# main.net
KiCad netlist of a schematic drawn in Altium Designer
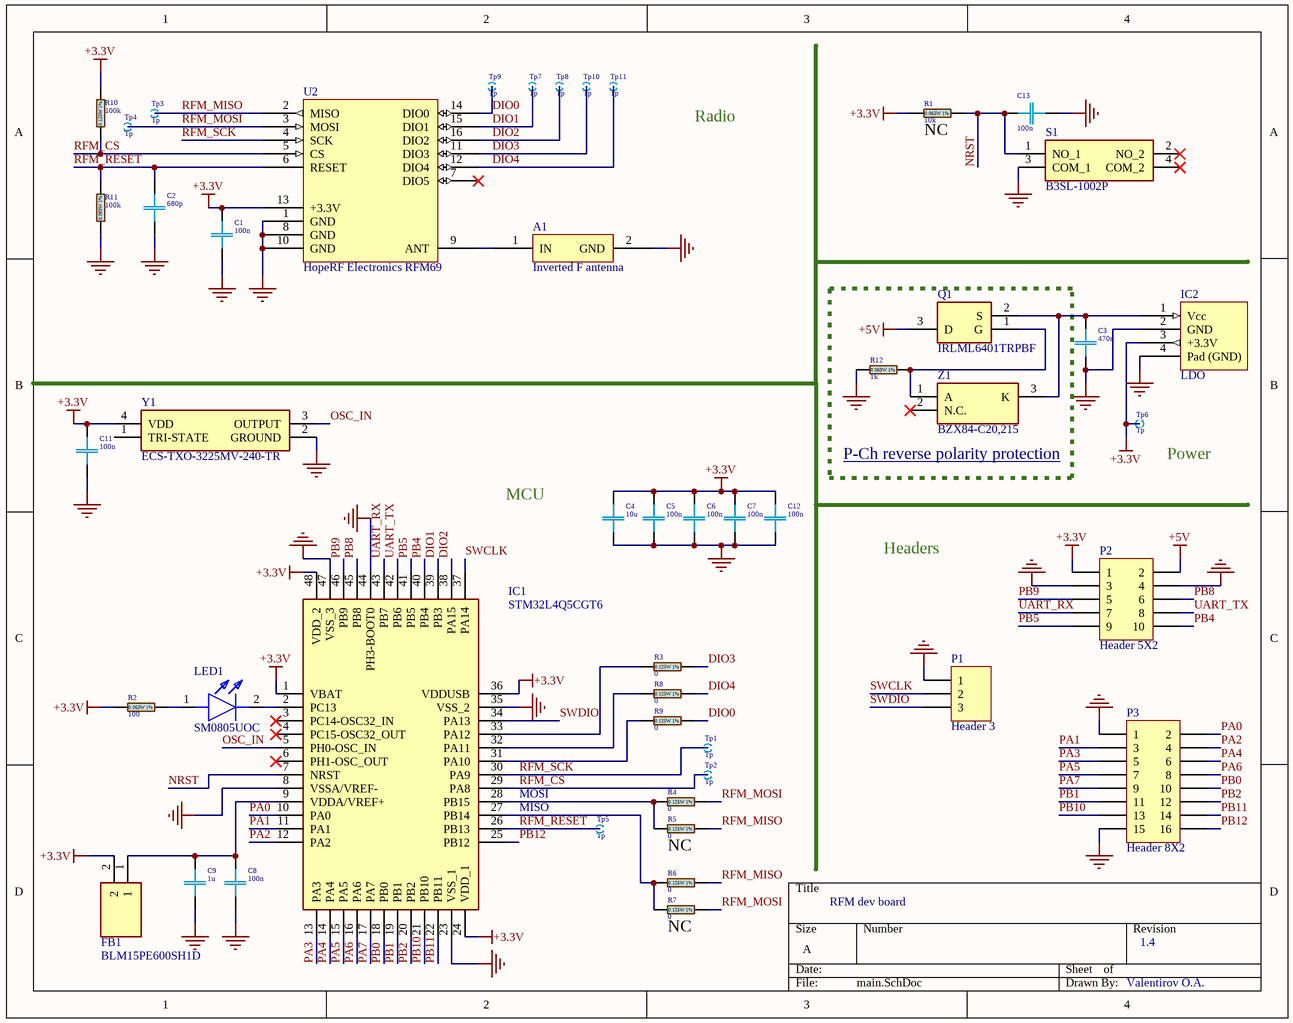
[diagram p0: main.SchDoc]

(export (version "E")
  (design (tool "Eeschema 10.0.6"))
  (components
    (comp (ref "A1")
      (value "Inverted F antenna")
      (footprint "Invertef_F-footprint")
      (libsource (lib "radio") (part "inverted_F"))
    )
    (comp (ref "C1")
      (value "100n")
      (footprint "C 0402(1005)x0.5")
      (description "SMD 0402     16V X5R 10%")
      (fields (field (name "MANUFACTURER") "Samsung") (field (name "PUBLISHER") "Hefest"))
      (libsource (lib "SMD Passive") (part "C 0402    16V X5R - 0*"))
    )
    (comp (ref "C2")
      (value "680p")
      (footprint "C 0402(1005)x0.5")
      (description "SMD 0402     16V X5R 10%")
      (fields (field (name "MANUFACTURER") "Samsung") (field (name "PUBLISHER") "Hefest"))
      (libsource (lib "SMD Passive") (part "C 0402    16V X5R - 0*"))
    )
    (comp (ref "C3")
      (value "470n")
      (footprint "C 0603(1608)x0.8")
      (description "SMD 0603     50V X7R   5%")
      (fields
        (field (name "PART NUMBER") "CL10B104JB8NNNC")
        (field (name "MANUFACTURER") "Samsung")
        (field (name "PUBLISHER") "Hefest")
      )
      (libsource (lib "SMD Passive") (part "C 0603    50V X7R - 100n"))
    )
    (comp (ref "C4")
      (value "10u")
      (footprint "C 0402(1005)x0.5")
      (description "SMD 0402     16V X5R 10%")
      (fields (field (name "MANUFACTURER") "Samsung") (field (name "PUBLISHER") "Hefest"))
      (libsource (lib "SMD Passive") (part "C 0402    16V X5R - 0*"))
    )
    (comp (ref "C5")
      (value "100n")
      (footprint "C 0402(1005)x0.5")
      (description "SMD 0402     16V X5R 10%")
      (fields (field (name "MANUFACTURER") "Samsung") (field (name "PUBLISHER") "Hefest"))
      (libsource (lib "SMD Passive") (part "C 0402    16V X5R - 0*"))
    )
    (comp (ref "C6")
      (value "100n")
      (footprint "C 0402(1005)x0.5")
      (description "SMD 0402     16V X5R 10%")
      (fields (field (name "MANUFACTURER") "Samsung") (field (name "PUBLISHER") "Hefest"))
      (libsource (lib "SMD Passive") (part "C 0402    16V X5R - 0*"))
    )
    (comp (ref "C7")
      (value "100n")
      (footprint "C 0402(1005)x0.5")
      (description "SMD 0402     16V X5R 10%")
      (fields (field (name "MANUFACTURER") "Samsung") (field (name "PUBLISHER") "Hefest"))
      (libsource (lib "SMD Passive") (part "C 0402    16V X5R - 0*"))
    )
    (comp (ref "C8")
      (value "100n")
      (footprint "C 0402(1005)x0.5")
      (description "SMD 0402     16V X5R 10%")
      (fields (field (name "MANUFACTURER") "Samsung") (field (name "PUBLISHER") "Hefest"))
      (libsource (lib "SMD Passive") (part "C 0402    16V X5R - 0*"))
    )
    (comp (ref "C9")
      (value "1u")
      (footprint "C 0402(1005)x0.5")
      (description "SMD 0402     16V X5R 10%")
      (fields (field (name "MANUFACTURER") "Samsung") (field (name "PUBLISHER") "Hefest"))
      (libsource (lib "SMD Passive") (part "C 0402    16V X5R - 0*"))
    )
    (comp (ref "C11")
      (value "100n")
      (footprint "C 0402(1005)x0.5")
      (description "SMD 0402     16V X5R 10%")
      (fields (field (name "MANUFACTURER") "Samsung") (field (name "PUBLISHER") "Hefest"))
      (libsource (lib "SMD Passive") (part "C 0402    16V X5R - 0*"))
    )
    (comp (ref "C12")
      (value "100n")
      (footprint "C 0402(1005)x0.5")
      (description "SMD 0402     16V X5R 10%")
      (fields (field (name "MANUFACTURER") "Samsung") (field (name "PUBLISHER") "Hefest"))
      (libsource (lib "SMD Passive") (part "C 0402    16V X5R - 0*"))
    )
    (comp (ref "C13")
      (value "100n")
      (footprint "C 0402(1005)x0.5")
      (description "SMD 0402     16V X5R 10%")
      (fields (field (name "MANUFACTURER") "Samsung") (field (name "PUBLISHER") "Hefest"))
      (libsource (lib "SMD Passive") (part "C 0402    16V X5R - 0*"))
    )
    (comp (ref "FB1")
      (value "BLM15PE600SH1D")
      (footprint "SamacSys:NFZ15SG152SN10B")
      (description "Ferrite Bead")
      (fields (field (name "MOUSER PART NUMBER") "81-BLM15PE600SH1D"))
      (libsource (lib "SamacSys") (part "BLM15PE600SH1D"))
    )
    (comp (ref "IC1")
      (value "STM32L4Q5CGT6")
      (footprint "SamacSys:QFP50P900X900X160-48N")
      (description "Integrated Circuit")
      (fields (field (name "MOUSER PART NUMBER") "511-STM32L4Q5CGT6"))
      (libsource (lib "SamacSys") (part "STM32L4Q5CGT6"))
    )
    (comp (ref "IC2")
      (value "LDO")
      (footprint "SOT230P700X180-4N")
      (description "LDO voltage regulator. In 4.5V - 5.5V. Out 3.3V")
      (libsource (lib "power") (part "LM3940IMP-3.3"))
    )
    (comp (ref "LED1")
      (value "SM0805UOC")
      (footprint "SamacSys:SM0805UOC")
      (description "LED")
      (fields (field (name "MOUSER PART NUMBER") "749-SM0805UOC"))
      (libsource (lib "SamacSys") (part "SM0805UOC"))
    )
    (comp (ref "P1")
      (value "Header 3")
      (footprint "HDR1X3")
      (description "Header, 3-Pin")
      (fields (field (name "PUBLISHER") "Altium Limited"))
      (libsource (lib "Miscellaneous Connectors") (part "Header 3"))
    )
    (comp (ref "P2")
      (value "Header 5X2")
      (footprint "HDR2X5")
      (description "Header, 5-Pin, Dual row")
      (fields (field (name "PUBLISHER") "Altium Limited"))
      (libsource (lib "Miscellaneous Connectors") (part "Header 5X2"))
    )
    (comp (ref "P3")
      (value "Header 8X2")
      (footprint "HDR2X8")
      (description "Header, 8-Pin, Dual row")
      (fields (field (name "PUBLISHER") "Altium Limited"))
      (libsource (lib "Miscellaneous Connectors") (part "Header 8X2"))
    )
    (comp (ref "Q1")
      (value "IRLML6401TRPBF")
      (footprint "SamacSys:SOT95P237X112-3N")
      (description "Transistor")
      (fields (field (name "MOUSER PART NUMBER") "942-IRLML6401TRPBF"))
      (libsource (lib "SamacSys") (part "IRLML6401TRPBF"))
    )
    (comp (ref "R1")
      (value "10k")
      (footprint "R 0402(1005)-1%")
      (description "SMD 0402 0.063W 1%   50V")
      (fields
        (field (name "MANUFACTURER") "YAGEO")
        (field (name "POWER") "0.0625W")
        (field (name "PUBLISHER") "Hefest")
      )
      (libsource (lib "") (part "R 0402-1%_1"))
    )
    (comp (ref "R2")
      (value "100")
      (footprint "R 0402(1005)-1%")
      (description "SMD 0402 0.063W 1%   50V")
      (fields
        (field (name "MANUFACTURER") "YAGEO")
        (field (name "POWER") "0.0625W")
        (field (name "PUBLISHER") "Hefest")
      )
      (libsource (lib "") (part "R 0402-1%_1"))
    )
    (comp (ref "R3")
      (value "0")
      (footprint "R 0805(2012)-1%")
      (description "SMD 0805 0.125W 1% 150V")
      (fields
        (field (name "MANUFACTURER") "YAGEO")
        (field (name "POWER") "0.125W")
        (field (name "PUBLISHER") "Hefest")
      )
      (libsource (lib "SMD Passive") (part "R 0805-1%"))
    )
    (comp (ref "R4")
      (value "0")
      (footprint "R 0805(2012)-1%")
      (description "SMD 0805 0.125W 1% 150V")
      (fields
        (field (name "MANUFACTURER") "YAGEO")
        (field (name "POWER") "0.125W")
        (field (name "PUBLISHER") "Hefest")
      )
      (libsource (lib "SMD Passive") (part "R 0805-1%"))
    )
    (comp (ref "R5")
      (value "0")
      (footprint "R 0805(2012)-1%")
      (description "SMD 0805 0.125W 1% 150V")
      (fields
        (field (name "MANUFACTURER") "YAGEO")
        (field (name "POWER") "0.125W")
        (field (name "PUBLISHER") "Hefest")
      )
      (libsource (lib "SMD Passive") (part "R 0805-1%"))
    )
    (comp (ref "R6")
      (value "0")
      (footprint "R 0805(2012)-1%")
      (description "SMD 0805 0.125W 1% 150V")
      (fields
        (field (name "MANUFACTURER") "YAGEO")
        (field (name "POWER") "0.125W")
        (field (name "PUBLISHER") "Hefest")
      )
      (libsource (lib "SMD Passive") (part "R 0805-1%"))
    )
    (comp (ref "R7")
      (value "0")
      (footprint "R 0805(2012)-1%")
      (description "SMD 0805 0.125W 1% 150V")
      (fields
        (field (name "MANUFACTURER") "YAGEO")
        (field (name "POWER") "0.125W")
        (field (name "PUBLISHER") "Hefest")
      )
      (libsource (lib "SMD Passive") (part "R 0805-1%"))
    )
    (comp (ref "R8")
      (value "0")
      (footprint "R 0805(2012)-1%")
      (description "SMD 0805 0.125W 1% 150V")
      (fields
        (field (name "MANUFACTURER") "YAGEO")
        (field (name "POWER") "0.125W")
        (field (name "PUBLISHER") "Hefest")
      )
      (libsource (lib "SMD Passive") (part "R 0805-1%"))
    )
    (comp (ref "R9")
      (value "0")
      (footprint "R 0805(2012)-1%")
      (description "SMD 0805 0.125W 1% 150V")
      (fields
        (field (name "MANUFACTURER") "YAGEO")
        (field (name "POWER") "0.125W")
        (field (name "PUBLISHER") "Hefest")
      )
      (libsource (lib "SMD Passive") (part "R 0805-1%"))
    )
    (comp (ref "R10")
      (value "100k")
      (footprint "R 0805(2012)-1%")
      (description "SMD 0805 0.125W 1% 150V")
      (fields
        (field (name "MANUFACTURER") "YAGEO")
        (field (name "POWER") "0.125W")
        (field (name "PUBLISHER") "Hefest")
      )
      (libsource (lib "") (part "R 0805-1%_1"))
    )
    (comp (ref "R11")
      (value "100k")
      (footprint "R 0402(1005)-1%")
      (description "SMD 0402 0.063W 1%   50V")
      (fields
        (field (name "MANUFACTURER") "YAGEO")
        (field (name "POWER") "0.0625W")
        (field (name "PUBLISHER") "Hefest")
      )
      (libsource (lib "SMD Passive") (part "R 0402-1%"))
    )
    (comp (ref "R12")
      (value "1k")
      (footprint "R 0402(1005)-1%")
      (description "SMD 0402 0.063W 1%   50V")
      (fields
        (field (name "MANUFACTURER") "YAGEO")
        (field (name "POWER") "0.0625W")
        (field (name "PUBLISHER") "Hefest")
      )
      (libsource (lib "") (part "R 0402-1%_1"))
    )
    (comp (ref "S1")
      (value "B3SL-1002P")
      (footprint "SamacSys:B3SL1002P")
      (description "Switch")
      (fields (field (name "MOUSER PART NUMBER") "653-B3SL-1002P"))
      (libsource (lib "SamacSys") (part "B3SL-1002P"))
    )
    (comp (ref "Tp1")
      (value "Tp")
      (footprint "Tp-0.5")
      (description "TestPoint")
      (fields (field (name "PUBLISHER") "Hefest"))
      (libsource (lib "SMD Passive") (part "Tp"))
    )
    (comp (ref "Tp2")
      (value "Tp")
      (footprint "Tp-0.5")
      (description "TestPoint")
      (fields (field (name "PUBLISHER") "Hefest"))
      (libsource (lib "SMD Passive") (part "Tp"))
    )
    (comp (ref "Tp3")
      (value "Tp")
      (footprint "Tp-0.5")
      (description "TestPoint")
      (fields (field (name "PUBLISHER") "Hefest"))
      (libsource (lib "SMD Passive") (part "Tp"))
    )
    (comp (ref "Tp4")
      (value "Tp")
      (footprint "Tp-0.5")
      (description "TestPoint")
      (fields (field (name "PUBLISHER") "Hefest"))
      (libsource (lib "SMD Passive") (part "Tp"))
    )
    (comp (ref "Tp5")
      (value "Tp")
      (footprint "Tp-0.5")
      (description "TestPoint")
      (fields (field (name "PUBLISHER") "Hefest"))
      (libsource (lib "SMD Passive") (part "Tp"))
    )
    (comp (ref "Tp6")
      (value "Tp")
      (footprint "Tp-0.5")
      (description "TestPoint")
      (fields (field (name "PUBLISHER") "Hefest"))
      (libsource (lib "SMD Passive") (part "Tp"))
    )
    (comp (ref "Tp7")
      (value "Tp")
      (footprint "Tp-0.5")
      (description "TestPoint")
      (fields (field (name "PUBLISHER") "Hefest"))
      (libsource (lib "SMD Passive") (part "Tp"))
    )
    (comp (ref "Tp8")
      (value "Tp")
      (footprint "Tp-0.5")
      (description "TestPoint")
      (fields (field (name "PUBLISHER") "Hefest"))
      (libsource (lib "SMD Passive") (part "Tp"))
    )
    (comp (ref "Tp9")
      (value "Tp")
      (footprint "Tp-0.5")
      (description "TestPoint")
      (fields (field (name "PUBLISHER") "Hefest"))
      (libsource (lib "SMD Passive") (part "Tp"))
    )
    (comp (ref "Tp10")
      (value "Tp")
      (footprint "Tp-0.5")
      (description "TestPoint")
      (fields (field (name "PUBLISHER") "Hefest"))
      (libsource (lib "SMD Passive") (part "Tp"))
    )
    (comp (ref "Tp11")
      (value "Tp")
      (footprint "Tp-0.5")
      (description "TestPoint")
      (fields (field (name "PUBLISHER") "Hefest"))
      (libsource (lib "SMD Passive") (part "Tp"))
    )
    (comp (ref "U2")
      (value "HopeRF Electronics RFM69")
      (footprint "CAC-200P1600X1600-16N")
      (libsource (lib "radio") (part "RFM69"))
    )
    (comp (ref "Y1")
      (value "ECS-TXO-3225MV-240-TR")
      (footprint "SamacSys:ECSTXO3225MV240TR")
      (description "Crystal or Oscillator")
      (fields (field (name "MOUSER PART NUMBER") "520-TXO-3225MV-240-T"))
      (libsource (lib "SamacSys") (part "ECS-TXO-3225MV-240-TR"))
    )
    (comp (ref "Z1")
      (value "BZX84-C20,215")
      (footprint "SamacSys:BZX84C20215")
      (description "Zener Diode")
      (fields (field (name "MOUSER PART NUMBER") "771-BZX84-C20-T/R"))
      (libsource (lib "SamacSys") (part "BZX84-C20,215"))
    )
  )
  (nets
    (net (code "1") (name "+3.3V") (class "Default")
      (node (ref "C1") (pin "1") (pinfunction "1_1") (pintype "passive"))
      (node (ref "C11") (pin "1") (pinfunction "1_1") (pintype "passive"))
      (node (ref "C12") (pin "1") (pinfunction "1_1") (pintype "passive"))
      (node (ref "C4") (pin "1") (pinfunction "1_1") (pintype "passive"))
      (node (ref "C5") (pin "1") (pinfunction "1_1") (pintype "passive"))
      (node (ref "C6") (pin "1") (pinfunction "1_1") (pintype "passive"))
      (node (ref "C7") (pin "1") (pinfunction "1_1") (pintype "passive"))
      (node (ref "FB1") (pin "2") (pinfunction "2_2") (pintype "passive"))
      (node (ref "IC1") (pin "1") (pinfunction "VBAT_1") (pintype "passive"))
      (node (ref "IC1") (pin "24") (pinfunction "VDD_1_24") (pintype "passive"))
      (node (ref "IC1") (pin "36") (pinfunction "VDDUSB_36") (pintype "passive"))
      (node (ref "IC1") (pin "48") (pinfunction "VDD_2_48") (pintype "passive"))
      (node (ref "IC2") (pin "3") (pinfunction "+3.3V_3") (pintype "output"))
      (node (ref "P2") (pin "1") (pinfunction "1_1") (pintype "passive"))
      (node (ref "R1") (pin "1") (pinfunction "1_1") (pintype "passive"))
      (node (ref "R10") (pin "2") (pinfunction "2_2") (pintype "passive"))
      (node (ref "R2") (pin "1") (pinfunction "1_1") (pintype "passive"))
      (node (ref "Tp6") (pin "1") (pinfunction "1_1") (pintype "passive"))
      (node (ref "U2") (pin "13") (pinfunction "+3.3V_13") (pintype "passive"))
      (node (ref "Y1") (pin "4") (pinfunction "VDD_4") (pintype "passive"))
    )
    (net (code "2") (name "+5V") (class "Default")
      (node (ref "P2") (pin "2") (pinfunction "2_2") (pintype "passive"))
      (node (ref "Q1") (pin "3") (pinfunction "D_3") (pintype "passive"))
    )
    (net (code "3") (name "/DIO0") (class "Default")
      (node (ref "R9") (pin "2") (pinfunction "2_2") (pintype "passive"))
      (node (ref "Tp9") (pin "1") (pinfunction "1_1") (pintype "passive"))
      (node (ref "U2") (pin "14") (pinfunction "DIO0_14") (pintype "bidirectional"))
    )
    (net (code "4") (name "/DIO1") (class "Default")
      (node (ref "IC1") (pin "39") (pinfunction "PB3_39") (pintype "passive"))
      (node (ref "Tp7") (pin "1") (pinfunction "1_1") (pintype "passive"))
      (node (ref "U2") (pin "15") (pinfunction "DIO1_15") (pintype "bidirectional"))
    )
    (net (code "5") (name "/DIO2") (class "Default")
      (node (ref "IC1") (pin "38") (pinfunction "PA15_38") (pintype "passive"))
      (node (ref "Tp8") (pin "1") (pinfunction "1_1") (pintype "passive"))
      (node (ref "U2") (pin "16") (pinfunction "DIO2_16") (pintype "bidirectional"))
    )
    (net (code "6") (name "/DIO3") (class "Default")
      (node (ref "R3") (pin "2") (pinfunction "2_2") (pintype "passive"))
      (node (ref "Tp10") (pin "1") (pinfunction "1_1") (pintype "passive"))
      (node (ref "U2") (pin "11") (pinfunction "DIO3_11") (pintype "bidirectional"))
    )
    (net (code "7") (name "/DIO4") (class "Default")
      (node (ref "R8") (pin "2") (pinfunction "2_2") (pintype "passive"))
      (node (ref "Tp11") (pin "1") (pinfunction "1_1") (pintype "passive"))
      (node (ref "U2") (pin "12") (pinfunction "DIO4_12") (pintype "bidirectional"))
    )
    (net (code "8") (name "/NRST") (class "Default")
      (node (ref "C13") (pin "1") (pinfunction "1_1") (pintype "passive"))
      (node (ref "IC1") (pin "7") (pinfunction "NRST_7") (pintype "passive"))
      (node (ref "R1") (pin "2") (pinfunction "2_2") (pintype "passive"))
      (node (ref "S1") (pin "1") (pinfunction "NO_1_1") (pintype "passive"))
    )
    (net (code "9") (name "/OSC_IN") (class "Default")
      (node (ref "IC1") (pin "5") (pinfunction "PH0-OSC_IN_5") (pintype "passive"))
      (node (ref "Y1") (pin "3") (pinfunction "OUTPUT_3") (pintype "passive"))
    )
    (net (code "10") (name "/PA0") (class "Default")
      (node (ref "IC1") (pin "10") (pinfunction "PA0_10") (pintype "passive"))
      (node (ref "P3") (pin "2") (pinfunction "2_2") (pintype "passive"))
    )
    (net (code "11") (name "/PA1") (class "Default")
      (node (ref "IC1") (pin "11") (pinfunction "PA1_11") (pintype "passive"))
      (node (ref "P3") (pin "3") (pinfunction "3_3") (pintype "passive"))
    )
    (net (code "12") (name "/PA2") (class "Default")
      (node (ref "IC1") (pin "12") (pinfunction "PA2_12") (pintype "passive"))
      (node (ref "P3") (pin "4") (pinfunction "4_4") (pintype "passive"))
    )
    (net (code "13") (name "/PA3") (class "Default")
      (node (ref "IC1") (pin "13") (pinfunction "PA3_13") (pintype "passive"))
      (node (ref "P3") (pin "5") (pinfunction "5_5") (pintype "passive"))
    )
    (net (code "14") (name "/PA4") (class "Default")
      (node (ref "IC1") (pin "14") (pinfunction "PA4_14") (pintype "passive"))
      (node (ref "P3") (pin "6") (pinfunction "6_6") (pintype "passive"))
    )
    (net (code "15") (name "/PA5") (class "Default")
      (node (ref "IC1") (pin "15") (pinfunction "PA5_15") (pintype "passive"))
      (node (ref "P3") (pin "7") (pinfunction "7_7") (pintype "passive"))
    )
    (net (code "16") (name "/PA6") (class "Default")
      (node (ref "IC1") (pin "16") (pinfunction "PA6_16") (pintype "passive"))
      (node (ref "P3") (pin "8") (pinfunction "8_8") (pintype "passive"))
    )
    (net (code "17") (name "/PA7") (class "Default")
      (node (ref "IC1") (pin "17") (pinfunction "PA7_17") (pintype "passive"))
      (node (ref "P3") (pin "9") (pinfunction "9_9") (pintype "passive"))
    )
    (net (code "18") (name "/PB0") (class "Default")
      (node (ref "IC1") (pin "18") (pinfunction "PB0_18") (pintype "passive"))
      (node (ref "P3") (pin "10") (pinfunction "10_10") (pintype "passive"))
    )
    (net (code "19") (name "/PB1") (class "Default")
      (node (ref "IC1") (pin "19") (pinfunction "PB1_19") (pintype "passive"))
      (node (ref "P3") (pin "11") (pinfunction "11_11") (pintype "passive"))
    )
    (net (code "20") (name "/PB2") (class "Default")
      (node (ref "IC1") (pin "20") (pinfunction "PB2_20") (pintype "passive"))
      (node (ref "P3") (pin "12") (pinfunction "12_12") (pintype "passive"))
    )
    (net (code "21") (name "/PB4") (class "Default")
      (node (ref "IC1") (pin "40") (pinfunction "PB4_40") (pintype "passive"))
      (node (ref "P2") (pin "10") (pinfunction "10_10") (pintype "passive"))
    )
    (net (code "22") (name "/PB5") (class "Default")
      (node (ref "IC1") (pin "41") (pinfunction "PB5_41") (pintype "passive"))
      (node (ref "P2") (pin "9") (pinfunction "9_9") (pintype "passive"))
    )
    (net (code "23") (name "/PB8") (class "Default")
      (node (ref "IC1") (pin "45") (pinfunction "PB8_45") (pintype "passive"))
      (node (ref "P2") (pin "6") (pinfunction "6_6") (pintype "passive"))
    )
    (net (code "24") (name "/PB9") (class "Default")
      (node (ref "IC1") (pin "46") (pinfunction "PB9_46") (pintype "passive"))
      (node (ref "P2") (pin "5") (pinfunction "5_5") (pintype "passive"))
    )
    (net (code "25") (name "/PB10") (class "Default")
      (node (ref "IC1") (pin "21") (pinfunction "PB10_21") (pintype "passive"))
      (node (ref "P3") (pin "13") (pinfunction "13_13") (pintype "passive"))
    )
    (net (code "26") (name "/PB11") (class "Default")
      (node (ref "IC1") (pin "22") (pinfunction "PB11_22") (pintype "passive"))
      (node (ref "P3") (pin "14") (pinfunction "14_14") (pintype "passive"))
    )
    (net (code "27") (name "/PB12") (class "Default")
      (node (ref "IC1") (pin "25") (pinfunction "PB12_25") (pintype "passive"))
      (node (ref "P3") (pin "16") (pinfunction "16_16") (pintype "passive"))
    )
    (net (code "28") (name "/RFM_CS") (class "Default")
      (node (ref "IC1") (pin "29") (pinfunction "PA8_29") (pintype "passive"))
      (node (ref "R10") (pin "1") (pinfunction "1_1") (pintype "passive"))
      (node (ref "Tp2") (pin "1") (pinfunction "1_1") (pintype "passive"))
      (node (ref "U2") (pin "5") (pinfunction "CS_5") (pintype "input"))
    )
    (net (code "29") (name "/RFM_MISO") (class "Default")
      (node (ref "R5") (pin "2") (pinfunction "2_2") (pintype "passive"))
      (node (ref "R6") (pin "2") (pinfunction "2_2") (pintype "passive"))
      (node (ref "Tp3") (pin "1") (pinfunction "1_1") (pintype "passive"))
      (node (ref "U2") (pin "2") (pinfunction "MISO_2") (pintype "output"))
    )
    (net (code "30") (name "/RFM_MOSI") (class "Default")
      (node (ref "R4") (pin "2") (pinfunction "2_2") (pintype "passive"))
      (node (ref "R7") (pin "2") (pinfunction "2_2") (pintype "passive"))
      (node (ref "Tp4") (pin "1") (pinfunction "1_1") (pintype "passive"))
      (node (ref "U2") (pin "3") (pinfunction "MOSI_3") (pintype "input"))
    )
    (net (code "31") (name "/RFM_RESET") (class "Default")
      (node (ref "C2") (pin "1") (pinfunction "1_1") (pintype "passive"))
      (node (ref "IC1") (pin "26") (pinfunction "PB13_26") (pintype "passive"))
      (node (ref "R11") (pin "2") (pinfunction "2_2") (pintype "passive"))
      (node (ref "Tp5") (pin "1") (pinfunction "1_1") (pintype "passive"))
      (node (ref "U2") (pin "6") (pinfunction "RESET_6") (pintype "passive"))
    )
    (net (code "32") (name "/RFM_SCK") (class "Default")
      (node (ref "IC1") (pin "30") (pinfunction "PA9_30") (pintype "passive"))
      (node (ref "Tp1") (pin "1") (pinfunction "1_1") (pintype "passive"))
      (node (ref "U2") (pin "4") (pinfunction "SCK_4") (pintype "input"))
    )
    (net (code "33") (name "/SWCLK") (class "Default")
      (node (ref "IC1") (pin "37") (pinfunction "PA14_37") (pintype "passive"))
      (node (ref "P1") (pin "2") (pinfunction "2_2") (pintype "passive"))
    )
    (net (code "34") (name "/SWDIO") (class "Default")
      (node (ref "IC1") (pin "34") (pinfunction "PA13_34") (pintype "passive"))
      (node (ref "P1") (pin "3") (pinfunction "3_3") (pintype "passive"))
    )
    (net (code "35") (name "/UART_RX") (class "Default")
      (node (ref "IC1") (pin "43") (pinfunction "PB7_43") (pintype "passive"))
      (node (ref "P2") (pin "7") (pinfunction "7_7") (pintype "passive"))
    )
    (net (code "36") (name "/UART_TX") (class "Default")
      (node (ref "IC1") (pin "42") (pinfunction "PB6_42") (pintype "passive"))
      (node (ref "P2") (pin "8") (pinfunction "8_8") (pintype "passive"))
    )
    (net (code "37") (name "GND") (class "Default")
      (node (ref "A1") (pin "2") (pinfunction "GND_2") (pintype "passive"))
      (node (ref "C1") (pin "2") (pinfunction "2_2") (pintype "passive"))
      (node (ref "C11") (pin "2") (pinfunction "2_2") (pintype "passive"))
      (node (ref "C12") (pin "2") (pinfunction "2_2") (pintype "passive"))
      (node (ref "C13") (pin "2") (pinfunction "2_2") (pintype "passive"))
      (node (ref "C2") (pin "2") (pinfunction "2_2") (pintype "passive"))
      (node (ref "C3") (pin "2") (pinfunction "2_2") (pintype "passive"))
      (node (ref "C4") (pin "2") (pinfunction "2_2") (pintype "passive"))
      (node (ref "C5") (pin "2") (pinfunction "2_2") (pintype "passive"))
      (node (ref "C6") (pin "2") (pinfunction "2_2") (pintype "passive"))
      (node (ref "C7") (pin "2") (pinfunction "2_2") (pintype "passive"))
      (node (ref "C8") (pin "2") (pinfunction "2_2") (pintype "passive"))
      (node (ref "C9") (pin "2") (pinfunction "2_2") (pintype "passive"))
      (node (ref "IC1") (pin "23") (pinfunction "VSS_1_23") (pintype "passive"))
      (node (ref "IC1") (pin "35") (pinfunction "VSS_2_35") (pintype "passive"))
      (node (ref "IC1") (pin "44") (pinfunction "PH3-BOOT0_44") (pintype "passive"))
      (node (ref "IC1") (pin "47") (pinfunction "VSS_3_47") (pintype "passive"))
      (node (ref "IC1") (pin "8") (pinfunction "VSSA/VREF-_8") (pintype "passive"))
      (node (ref "IC2") (pin "2") (pinfunction "GND_2") (pintype "passive"))
      (node (ref "IC2") (pin "4") (pinfunction "Pad_(GND)_4") (pintype "passive"))
      (node (ref "P1") (pin "1") (pinfunction "1_1") (pintype "passive"))
      (node (ref "P2") (pin "3") (pinfunction "3_3") (pintype "passive"))
      (node (ref "P2") (pin "4") (pinfunction "4_4") (pintype "passive"))
      (node (ref "P3") (pin "1") (pinfunction "1_1") (pintype "passive"))
      (node (ref "P3") (pin "15") (pinfunction "15_15") (pintype "passive"))
      (node (ref "R11") (pin "1") (pinfunction "1_1") (pintype "passive"))
      (node (ref "R12") (pin "1") (pinfunction "1_1") (pintype "passive"))
      (node (ref "S1") (pin "3") (pinfunction "COM_1_3") (pintype "passive"))
      (node (ref "U2") (pin "1") (pinfunction "GND_1") (pintype "passive"))
      (node (ref "U2") (pin "10") (pinfunction "GND_10") (pintype "passive"))
      (node (ref "U2") (pin "8") (pinfunction "GND_8") (pintype "passive"))
      (node (ref "Y1") (pin "2") (pinfunction "GROUND_2") (pintype "passive"))
    )
    (net (code "38") (name "Net-(A1-IN)") (class "Default")
      (node (ref "A1") (pin "1") (pinfunction "IN_1") (pintype "passive"))
      (node (ref "U2") (pin "9") (pinfunction "ANT_9") (pintype "passive"))
    )
    (net (code "39") (name "Net-(IC1-PA10)") (class "Default")
      (node (ref "IC1") (pin "31") (pinfunction "PA10_31") (pintype "passive"))
      (node (ref "R9") (pin "1") (pinfunction "1_1") (pintype "passive"))
    )
    (net (code "40") (name "Net-(IC1-PA11)") (class "Default")
      (node (ref "IC1") (pin "32") (pinfunction "PA11_32") (pintype "passive"))
      (node (ref "R8") (pin "1") (pinfunction "1_1") (pintype "passive"))
    )
    (net (code "41") (name "Net-(IC1-PA12)") (class "Default")
      (node (ref "IC1") (pin "33") (pinfunction "PA12_33") (pintype "passive"))
      (node (ref "R3") (pin "1") (pinfunction "1_1") (pintype "passive"))
    )
    (net (code "42") (name "Net-(IC1-PB14)") (class "Default")
      (node (ref "IC1") (pin "27") (pinfunction "PB14_27") (pintype "passive"))
      (node (ref "R6") (pin "1") (pinfunction "1_1") (pintype "passive"))
      (node (ref "R7") (pin "1") (pinfunction "1_1") (pintype "passive"))
    )
    (net (code "43") (name "Net-(IC1-PB15)") (class "Default")
      (node (ref "IC1") (pin "28") (pinfunction "PB15_28") (pintype "passive"))
      (node (ref "R4") (pin "1") (pinfunction "1_1") (pintype "passive"))
      (node (ref "R5") (pin "1") (pinfunction "1_1") (pintype "passive"))
    )
    (net (code "44") (name "Net-(IC1-PC13)") (class "Default")
      (node (ref "IC1") (pin "2") (pinfunction "PC13_2") (pintype "passive"))
      (node (ref "LED1") (pin "2") (pinfunction "K_2") (pintype "passive"))
    )
    (net (code "45") (name "Net-(IC1-VDDA{slash}VREF+)") (class "Default")
      (node (ref "C8") (pin "1") (pinfunction "1_1") (pintype "passive"))
      (node (ref "C9") (pin "1") (pinfunction "1_1") (pintype "passive"))
      (node (ref "FB1") (pin "1") (pinfunction "1_1") (pintype "passive"))
      (node (ref "IC1") (pin "9") (pinfunction "VDDA/VREF+_9") (pintype "passive"))
    )
    (net (code "46") (name "Net-(IC2-Vcc)") (class "Default")
      (node (ref "C3") (pin "1") (pinfunction "1_1") (pintype "passive"))
      (node (ref "IC2") (pin "1") (pinfunction "Vcc_1") (pintype "input"))
      (node (ref "Q1") (pin "2") (pinfunction "S_2") (pintype "passive"))
      (node (ref "Z1") (pin "3") (pinfunction "K_3") (pintype "passive"))
    )
    (net (code "47") (name "Net-(LED1-A)") (class "Default")
      (node (ref "LED1") (pin "1") (pinfunction "A_1") (pintype "passive"))
      (node (ref "R2") (pin "2") (pinfunction "2_2") (pintype "passive"))
    )
    (net (code "48") (name "Net-(Q1-G)") (class "Default")
      (node (ref "Q1") (pin "1") (pinfunction "G_1") (pintype "passive"))
      (node (ref "R12") (pin "2") (pinfunction "2_2") (pintype "passive"))
      (node (ref "Z1") (pin "1") (pinfunction "A_1") (pintype "passive"))
    )
    (net (code "49") (name "unconnected-(IC1-PC14-OSC32_IN-Pad3)") (class "Default")
      (node (ref "IC1") (pin "3") (pinfunction "PC14-OSC32_IN_3") (pintype "passive+no_connect"))
    )
    (net (code "50") (name "unconnected-(IC1-PC15-OSC32_OUT-Pad4)") (class "Default")
      (node (ref "IC1") (pin "4") (pinfunction "PC15-OSC32_OUT_4") (pintype "passive+no_connect"))
    )
    (net (code "51") (name "unconnected-(IC1-PH1-OSC_OUT-Pad6)") (class "Default")
      (node (ref "IC1") (pin "6") (pinfunction "PH1-OSC_OUT_6") (pintype "passive+no_connect"))
    )
    (net (code "52") (name "unconnected-(S1-COM_2-Pad4)") (class "Default")
      (node (ref "S1") (pin "4") (pinfunction "COM_2_4") (pintype "passive+no_connect"))
    )
    (net (code "53") (name "unconnected-(S1-NO_2-Pad2)") (class "Default")
      (node (ref "S1") (pin "2") (pinfunction "NO_2_2") (pintype "passive+no_connect"))
    )
    (net (code "54") (name "unconnected-(U2-DIO5-Pad7)") (class "Default")
      (node (ref "U2") (pin "7") (pinfunction "DIO5_7") (pintype "bidirectional+no_connect"))
    )
    (net (code "55") (name "unconnected-(Y1-TRI-STATE-Pad1)") (class "Default")
      (node (ref "Y1") (pin "1") (pinfunction "TRI-STATE_1") (pintype "passive"))
    )
    (net (code "56") (name "unconnected-(Z1-N.C.-Pad2)") (class "Default")
      (node (ref "Z1") (pin "2") (pinfunction "N.C._2") (pintype "passive+no_connect"))
    )
  )
)
